# Smart_Lora_Node.net
KiCad netlist of a schematic drawn in Altium Designer
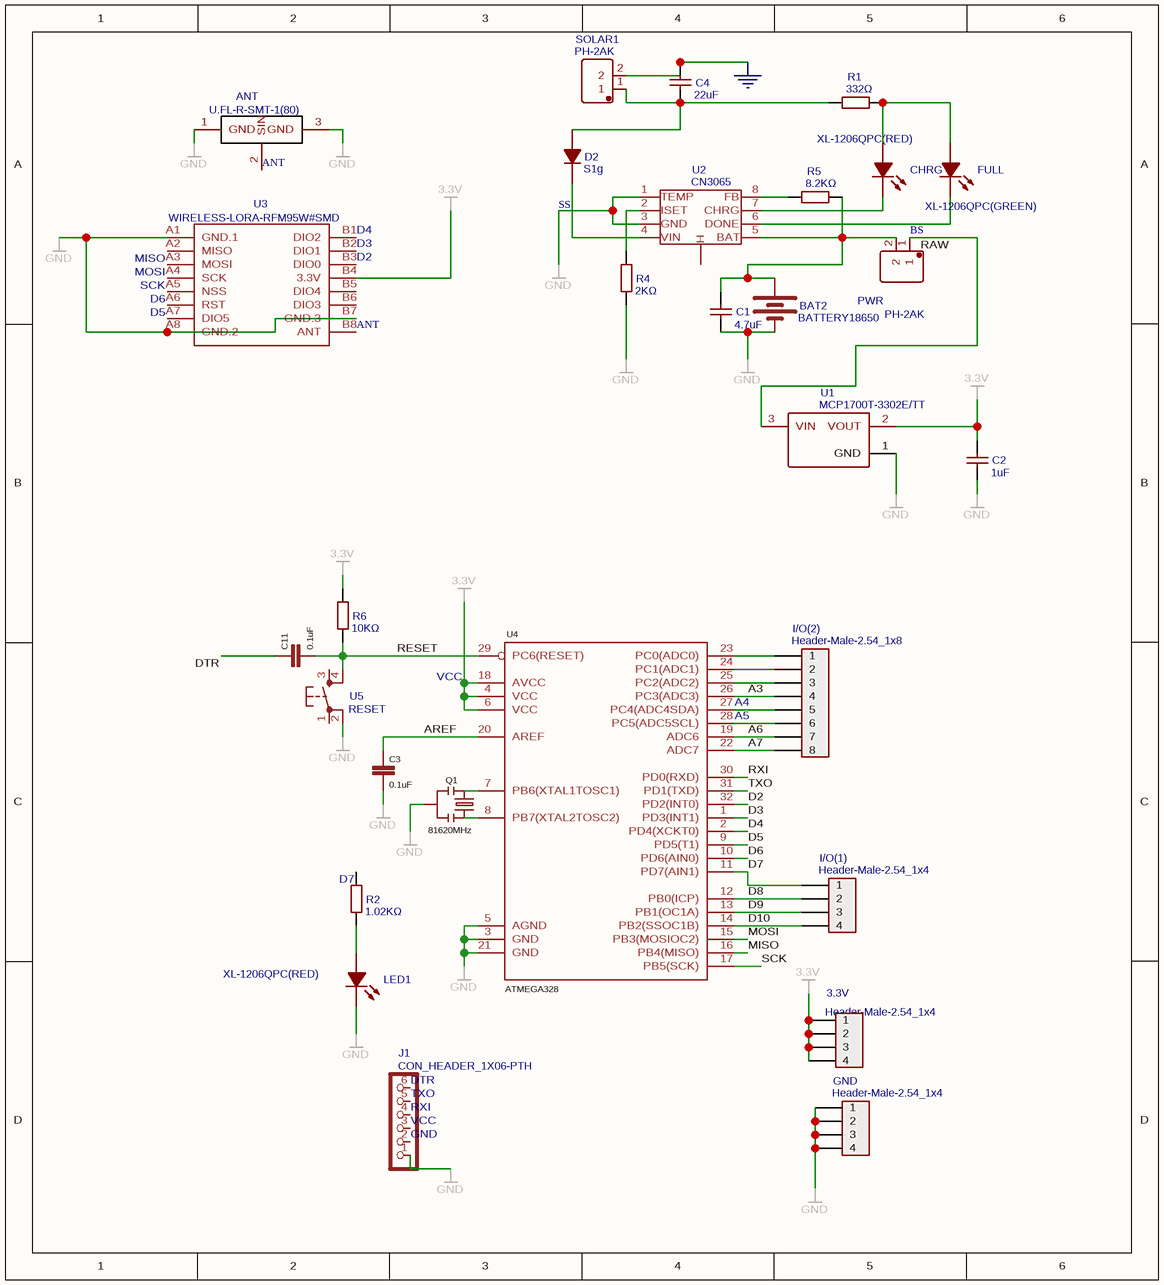
[diagram p0: Smart+Lora+Node.schdoc]

(export (version "E")
  (design (tool "Eeschema 10.0.6"))
  (components
    (comp (ref "3.3V")
      (value "Header-Male-2.54_1x4")
      (fields
        (field (name "BOM_MANUFACTURER PART") "Headers??Pins 1*4P")
        (field (name "BOM_SUPPLIER PART") "C59481")
      )
      (libsource (lib "altium-import") (part "root_0_Header-Male-2.54_1x4_"))
    )
    (comp (ref "ANT")
      (value "U.FL-R-SMT-1(80)")
      (fields (field (name "BOM_SUPPLIER PART") "C88374"))
      (libsource (lib "altium-import") (part "root_0_U.FL-R-SMT-1(80)_"))
    )
    (comp (ref "BAT2")
      (value "BATTERY18650")
      (description "Battery Holders")
      (fields (field (name "BOM_MANUFACTURER PART") "?") (field (name "CONTRIBUTOR") "SparkFun"))
      (libsource (lib "altium-import") (part "root_3_BATTERY18650_"))
    )
    (comp (ref "C1")
      (value "4.7uF")
      (fields
        (field (name "VOLTAGE") "50V")
        (field (name "TOLERANCE") "±10%")
        (field (name "BOM_MANUFACTURER PART") "1206B475K500NT")
      )
      (libsource (lib "altium-import") (part "root_1_4.7uF_"))
    )
    (comp (ref "C2")
      (value "1uF")
      (fields
        (field (name "VOLTAGE") "50V")
        (field (name "TOLERANCE") "±10%")
        (field (name "BOM_MANUFACTURER PART") "0805B105K500NT")
      )
      (libsource (lib "altium-import") (part "root_1_1uF_"))
    )
    (comp (ref "C3") (value "0.1uF") (libsource (lib "altium-import") (part "root_2_0.1uF_")))
    (comp (ref "C4")
      (value "22uF")
      (fields
        (field (name "VOLTAGE") "10V")
        (field (name "TOLERANCE") "±10%")
        (field (name "BOM_MANUFACTURER PART") "1206X226K100NT")
      )
      (libsource (lib "altium-import") (part "root_1_22uF_"))
    )
    (comp (ref "C11") (value "0.1uF") (libsource (lib "altium-import") (part "root_3_0.1uF_")))
    (comp (ref "CHRG")
      (value "XL-1206QPC(RED)")
      (fields (field (name "BOM_MANUFACTURER PART") "XL-1206QPC") (field (name "BOM_SUPPLIER PART") "C10781"))
      (libsource (lib "altium-import") (part "root_3_XL-1206QPC(RED)_"))
    )
    (comp (ref "D2")
      (value "S1g")
      (fields (field (name "BOM_SUPPLIER PART") "C19153"))
      (libsource (lib "altium-import") (part "root_3_S1g_"))
    )
    (comp (ref "FULL")
      (value "XL-1206QPC(GREEN)")
      (fields (field (name "BOM_MANUFACTURER PART") "XL-1206QPC") (field (name "BOM_SUPPLIER PART") "C10781"))
      (libsource (lib "altium-import") (part "root_3_XL-1206QPC(GREEN)_"))
    )
    (comp (ref "GND")
      (value "Header-Male-2.54_1x4")
      (fields
        (field (name "BOM_MANUFACTURER PART") "Headers??Pins 1*4P")
        (field (name "BOM_SUPPLIER PART") "C59481")
      )
      (libsource (lib "altium-import") (part "root_0_Header-Male-2.54_1x4_"))
    )
    (comp (ref "I/O(1)")
      (value "Header-Male-2.54_1x4")
      (fields
        (field (name "BOM_MANUFACTURER PART") "Headers??Pins 1*4P")
        (field (name "BOM_SUPPLIER PART") "C59481")
      )
      (libsource (lib "altium-import") (part "root_0_Header-Male-2.54_1x4_"))
    )
    (comp (ref "I/O(2)")
      (value "Header-Male-2.54_1x8")
      (fields
        (field (name "BOM_MANUFACTURER PART") "Header2.54mm 1*8P")
        (field (name "BOM_SUPPLIER PART") "C49256")
      )
      (libsource (lib "altium-import") (part "root_0_Header-Male-2.54_1x8_"))
    )
    (comp (ref "J1")
      (value "CON_HEADER_1X06-PTH")
      (fields (field (name "BOM_MANUFACTURER PART") "?") (field (name "CONTRIBUTOR") "DangerousPrototype"))
      (libsource (lib "altium-import") (part "root_2_CON_HEADER_1X06-PTH_"))
    )
    (comp (ref "LED1")
      (value "XL-1206QPC(RED)")
      (fields (field (name "BOM_MANUFACTURER PART") "XL-1206QPC") (field (name "BOM_SUPPLIER PART") "C10781"))
      (libsource (lib "altium-import") (part "root_3_XL-1206QPC(RED)_"))
    )
    (comp (ref "PWR")
      (value "PH-2AK")
      (fields (field (name "BOM_MANUFACTURER PART") "?") (field (name "BOM_SUPPLIER PART") "C8886"))
      (libsource (lib "altium-import") (part "root_3_PH-2AK_"))
    )
    (comp (ref "Q1") (value "81620MHz") (libsource (lib "altium-import") (part "root_3_81620MHz_")))
    (comp (ref "R1")
      (value "332Ω")
      (fields
        (field (name "POWER") "1/8W")
        (field (name "TOLERANCE") "±1%")
        (field (name "BOM_MANUFACTURER PART") "0805W8F3320T5E")
      )
      (libsource (lib "altium-import") (part "root_0_332Ω_"))
    )
    (comp (ref "R2")
      (value "1.02KΩ")
      (fields
        (field (name "POWER") "1/8W")
        (field (name "TOLERANCE") "±1%")
        (field (name "BOM_MANUFACTURER PART") "0805W8F1021T5E")
      )
      (libsource (lib "altium-import") (part "root_1_1.02KΩ_"))
    )
    (comp (ref "R4")
      (value "2KΩ")
      (fields
        (field (name "POWER") "1/8W")
        (field (name "TOLERANCE") "±5%")
        (field (name "BOM_MANUFACTURER PART") "0805W8J0202T5E")
      )
      (libsource (lib "altium-import") (part "root_1_2KΩ_"))
    )
    (comp (ref "R5")
      (value "8.2KΩ")
      (fields
        (field (name "POWER") "1/4W")
        (field (name "TOLERANCE") "±5%")
        (field (name "BOM_MANUFACTURER PART") "1206W4J0822T5E")
      )
      (libsource (lib "altium-import") (part "root_0_8.2KΩ_"))
    )
    (comp (ref "R6")
      (value "10KΩ")
      (fields
        (field (name "POWER") "1/8W")
        (field (name "TOLERANCE") "±5%")
        (field (name "BOM_MANUFACTURER PART") "0805W8J0103T5E")
      )
      (libsource (lib "altium-import") (part "root_1_10KΩ_"))
    )
    (comp (ref "SOLAR1")
      (value "PH-2AK")
      (fields (field (name "BOM_MANUFACTURER PART") "?") (field (name "BOM_SUPPLIER PART") "C8886"))
      (libsource (lib "altium-import") (part "root_2_PH-2AK_"))
    )
    (comp (ref "U1")
      (value "MCP1700T-3302E/TT")
      (fields (field (name "BOM_SUPPLIER PART") "C39051"))
      (libsource (lib "altium-import") (part "root_0_MCP1700T-3302E/TT_"))
    )
    (comp (ref "U2")
      (value "CN3065")
      (description "SMD PMIC;Liner;Li-Ion/Pol;Charge;4.2V;1-cell")
      (libsource (lib "altium-import") (part "root_0_CN3065_"))
    )
    (comp (ref "U3")
      (value "WIRELESS-LORA-RFM95W#SMD")
      (description "868915 MHz LoRa Radio Transceiver Module based on SX1276 chip")
      (fields
        (field (name "BOM_MANUFACTURER PART") "RFM95W-868S2")
        (field (name "BOM_SUPPLIER PART") "125-1259")
      )
      (libsource (lib "altium-import") (part "root_0_WIRELESS-LORA-RFM95W#SMD_"))
    )
    (comp (ref "U4") (value "ATMEGA328") (libsource (lib "altium-import") (part "root_0_ATMEGA328_")))
    (comp (ref "U5")
      (value "RESET")
      (description "Tactile Switch 4 Pins, SPST NO PTS645SM43SMTR92")
      (fields (field (name "BOM_MANUFACTURER PART") "?"))
      (libsource (lib "altium-import") (part "root_1_RESET_"))
    )
  )
  (nets
    (net (code "1") (name "/A3") (class "Default")
      (node (ref "I/O(2)") (pin "4") (pinfunction "4_4") (pintype "passive"))
      (node (ref "U4") (pin "26") (pinfunction "PC3(ADC3)_26") (pintype "passive"))
    )
    (net (code "2") (name "/A4") (class "Default")
      (node (ref "I/O(2)") (pin "5") (pinfunction "5_5") (pintype "passive"))
      (node (ref "U4") (pin "27") (pinfunction "PC4(ADC4SDA)_27") (pintype "passive"))
    )
    (net (code "3") (name "/A5") (class "Default")
      (node (ref "I/O(2)") (pin "6") (pinfunction "6_6") (pintype "passive"))
      (node (ref "U4") (pin "28") (pinfunction "PC5(ADC5SCL)_28") (pintype "passive"))
    )
    (net (code "4") (name "/A6") (class "Default")
      (node (ref "I/O(2)") (pin "7") (pinfunction "7_7") (pintype "passive"))
      (node (ref "U4") (pin "19") (pinfunction "ADC6_19") (pintype "passive"))
    )
    (net (code "5") (name "/A7") (class "Default")
      (node (ref "I/O(2)") (pin "8") (pinfunction "8_8") (pintype "passive"))
      (node (ref "U4") (pin "22") (pinfunction "ADC7_22") (pintype "passive"))
    )
    (net (code "6") (name "/ANT") (class "Default")
      (node (ref "ANT") (pin "2") (pinfunction "SIN_2") (pintype "passive"))
      (node (ref "U3") (pin "B8") (pinfunction "ANT_B8") (pintype "passive"))
    )
    (net (code "7") (name "/AREF") (class "Default")
      (node (ref "C3") (pin "2") (pinfunction "2_2") (pintype "passive"))
      (node (ref "U4") (pin "20") (pinfunction "AREF_20") (pintype "passive"))
    )
    (net (code "8") (name "/BS") (class "Default")
      (node (ref "PWR") (pin "1") (pinfunction "1_1") (pintype "passive"))
      (node (ref "U1") (pin "3") (pinfunction "VIN_3") (pintype "passive"))
    )
    (net (code "9") (name "/D2") (class "Default")
      (node (ref "U3") (pin "B3") (pinfunction "DIO0_B3") (pintype "passive"))
      (node (ref "U4") (pin "32") (pinfunction "PD2(INT0)_32") (pintype "passive"))
    )
    (net (code "10") (name "/D3") (class "Default")
      (node (ref "U3") (pin "B2") (pinfunction "DIO1_B2") (pintype "passive"))
      (node (ref "U4") (pin "1") (pinfunction "PD3(INT1)_1") (pintype "passive"))
    )
    (net (code "11") (name "/D4") (class "Default")
      (node (ref "U3") (pin "B1") (pinfunction "DIO2_B1") (pintype "passive"))
      (node (ref "U4") (pin "2") (pinfunction "PD4(XCKT0)_2") (pintype "passive"))
    )
    (net (code "12") (name "/D5") (class "Default")
      (node (ref "U3") (pin "A6") (pinfunction "RST_A6") (pintype "passive"))
      (node (ref "U4") (pin "9") (pinfunction "PD5(T1)_9") (pintype "passive"))
    )
    (net (code "13") (name "/D6") (class "Default")
      (node (ref "U3") (pin "A5") (pinfunction "NSS_A5") (pintype "passive"))
      (node (ref "U4") (pin "10") (pinfunction "PD6(AIN0)_10") (pintype "passive"))
    )
    (net (code "14") (name "/D7") (class "Default")
      (node (ref "I/O(1)") (pin "1") (pinfunction "1_1") (pintype "passive"))
      (node (ref "R2") (pin "2") (pinfunction "2_2") (pintype "passive"))
      (node (ref "U4") (pin "11") (pinfunction "PD7(AIN1)_11") (pintype "passive"))
    )
    (net (code "15") (name "/D8") (class "Default")
      (node (ref "I/O(1)") (pin "2") (pinfunction "2_2") (pintype "passive"))
      (node (ref "U4") (pin "12") (pinfunction "PB0(ICP)_12") (pintype "passive"))
    )
    (net (code "16") (name "/D9") (class "Default")
      (node (ref "I/O(1)") (pin "3") (pinfunction "3_3") (pintype "passive"))
      (node (ref "U4") (pin "13") (pinfunction "PB1(OC1A)_13") (pintype "passive"))
    )
    (net (code "17") (name "/D10") (class "Default")
      (node (ref "I/O(1)") (pin "4") (pinfunction "4_4") (pintype "passive"))
      (node (ref "U4") (pin "14") (pinfunction "PB2(SSOC1B)_14") (pintype "passive"))
    )
    (net (code "18") (name "/DTR") (class "Default")
      (node (ref "C11") (pin "2") (pinfunction "2_2") (pintype "passive"))
      (node (ref "J1") (pin "6") (pinfunction "6_6") (pintype "passive"))
    )
    (net (code "19") (name "/MISO") (class "Default")
      (node (ref "U3") (pin "A2") (pinfunction "MISO_A2") (pintype "passive"))
      (node (ref "U4") (pin "16") (pinfunction "PB4(MISO)_16") (pintype "passive"))
    )
    (net (code "20") (name "/MOSI") (class "Default")
      (node (ref "U3") (pin "A3") (pinfunction "MOSI_A3") (pintype "passive"))
      (node (ref "U4") (pin "15") (pinfunction "PB3(MOSIOC2)_15") (pintype "passive"))
    )
    (net (code "21") (name "/RESET") (class "Default")
      (node (ref "C11") (pin "1") (pinfunction "1_1") (pintype "passive"))
      (node (ref "R6") (pin "1") (pinfunction "1_1") (pintype "passive"))
      (node (ref "U4") (pin "29") (pinfunction "PC6(RESET)_29") (pintype "passive"))
      (node (ref "U5") (pin "4") (pinfunction "4_4") (pintype "passive"))
    )
    (net (code "22") (name "/RXI") (class "Default")
      (node (ref "J1") (pin "4") (pinfunction "4_4") (pintype "passive"))
      (node (ref "U4") (pin "30") (pinfunction "PD0(RXD)_30") (pintype "passive"))
    )
    (net (code "23") (name "/SCK") (class "Default")
      (node (ref "U3") (pin "A4") (pinfunction "SCK_A4") (pintype "passive"))
      (node (ref "U4") (pin "17") (pinfunction "PB5(SCK)_17") (pintype "passive"))
    )
    (net (code "24") (name "/SS") (class "Default")
      (node (ref "D2") (pin "2") (pinfunction "K_2") (pintype "passive"))
      (node (ref "U2") (pin "4") (pinfunction "VIN_4") (pintype "passive"))
    )
    (net (code "25") (name "/TXO") (class "Default")
      (node (ref "J1") (pin "5") (pinfunction "5_5") (pintype "passive"))
      (node (ref "U4") (pin "31") (pinfunction "PD1(TXD)_31") (pintype "passive"))
    )
    (net (code "26") (name "3.3V") (class "Default")
      (node (ref "3.3V") (pin "1") (pinfunction "1_1") (pintype "passive"))
      (node (ref "3.3V") (pin "2") (pinfunction "2_2") (pintype "passive"))
      (node (ref "3.3V") (pin "3") (pinfunction "3_3") (pintype "passive"))
      (node (ref "3.3V") (pin "4") (pinfunction "4_4") (pintype "passive"))
      (node (ref "C2") (pin "2") (pinfunction "2_2") (pintype "passive"))
      (node (ref "J1") (pin "3") (pinfunction "3_3") (pintype "passive"))
      (node (ref "R6") (pin "2") (pinfunction "2_2") (pintype "passive"))
      (node (ref "U1") (pin "2") (pinfunction "VOUT_2") (pintype "passive"))
      (node (ref "U3") (pin "B4") (pinfunction "3.3V_B4") (pintype "passive"))
      (node (ref "U4") (pin "18") (pinfunction "AVCC_18") (pintype "passive"))
      (node (ref "U4") (pin "4") (pinfunction "VCC_4") (pintype "passive"))
      (node (ref "U4") (pin "6") (pinfunction "VCC_6") (pintype "passive"))
    )
    (net (code "27") (name "GND") (class "Default")
      (node (ref "ANT") (pin "1") (pinfunction "GND_1") (pintype "passive"))
      (node (ref "ANT") (pin "3") (pinfunction "GND_3") (pintype "passive"))
      (node (ref "BAT2") (pin "-GND") (pinfunction "-_-GND") (pintype "passive"))
      (node (ref "C1") (pin "1") (pinfunction "1_1") (pintype "passive"))
      (node (ref "C2") (pin "1") (pinfunction "1_1") (pintype "passive"))
      (node (ref "C3") (pin "1") (pinfunction "1_1") (pintype "passive"))
      (node (ref "C4") (pin "2") (pinfunction "2_2") (pintype "passive"))
      (node (ref "GND") (pin "1") (pinfunction "1_1") (pintype "passive"))
      (node (ref "GND") (pin "2") (pinfunction "2_2") (pintype "passive"))
      (node (ref "GND") (pin "3") (pinfunction "3_3") (pintype "passive"))
      (node (ref "GND") (pin "4") (pinfunction "4_4") (pintype "passive"))
      (node (ref "J1") (pin "1") (pinfunction "1_1") (pintype "passive"))
      (node (ref "J1") (pin "2") (pinfunction "2_2") (pintype "passive"))
      (node (ref "LED1") (pin "1") (pinfunction "K_1") (pintype "passive"))
      (node (ref "Q1") (pin "2") (pinfunction "2_2") (pintype "passive"))
      (node (ref "R4") (pin "1") (pinfunction "1_1") (pintype "passive"))
      (node (ref "SOLAR1") (pin "2") (pinfunction "2_2") (pintype "passive"))
      (node (ref "U1") (pin "1") (pinfunction "GND_1") (pintype "passive"))
      (node (ref "U2") (pin "1") (pinfunction "TEMP_1") (pintype "passive"))
      (node (ref "U2") (pin "3") (pinfunction "GND_3") (pintype "passive"))
      (node (ref "U3") (pin "A1") (pinfunction "GND.1_A1") (pintype "passive"))
      (node (ref "U3") (pin "A8") (pinfunction "GND.2_A8") (pintype "passive"))
      (node (ref "U3") (pin "B7") (pinfunction "GND.3_B7") (pintype "passive"))
      (node (ref "U4") (pin "21") (pinfunction "GND_21") (pintype "passive"))
      (node (ref "U4") (pin "3") (pinfunction "GND_3") (pintype "passive"))
      (node (ref "U4") (pin "5") (pinfunction "AGND_5") (pintype "passive"))
      (node (ref "U5") (pin "2") (pinfunction "2_2") (pintype "passive"))
    )
    (net (code "28") (name "Net-(BAT2-+)") (class "Default")
      (node (ref "BAT2") (pin "+BAT") (pinfunction "+_+BAT") (pintype "passive"))
      (node (ref "C1") (pin "2") (pinfunction "2_2") (pintype "passive"))
      (node (ref "PWR") (pin "2") (pinfunction "2_2") (pintype "passive"))
      (node (ref "R5") (pin "2") (pinfunction "2_2") (pintype "passive"))
      (node (ref "U2") (pin "5") (pinfunction "BAT_5") (pintype "passive"))
    )
    (net (code "29") (name "Net-(CHRG-A)") (class "Default")
      (node (ref "CHRG") (pin "2") (pinfunction "A_2") (pintype "passive"))
      (node (ref "FULL") (pin "2") (pinfunction "A_2") (pintype "passive"))
      (node (ref "R1") (pin "2") (pinfunction "2_2") (pintype "passive"))
    )
    (net (code "30") (name "Net-(CHRG-K)") (class "Default")
      (node (ref "CHRG") (pin "1") (pinfunction "K_1") (pintype "passive"))
      (node (ref "U2") (pin "7") (pinfunction "CHRG_7") (pintype "passive"))
    )
    (net (code "31") (name "Net-(D2-A)") (class "Default")
      (node (ref "C4") (pin "1") (pinfunction "1_1") (pintype "passive"))
      (node (ref "D2") (pin "1") (pinfunction "A_1") (pintype "passive"))
      (node (ref "R1") (pin "1") (pinfunction "1_1") (pintype "passive"))
      (node (ref "SOLAR1") (pin "1") (pinfunction "1_1") (pintype "passive"))
    )
    (net (code "32") (name "Net-(FULL-K)") (class "Default")
      (node (ref "FULL") (pin "1") (pinfunction "K_1") (pintype "passive"))
      (node (ref "U2") (pin "6") (pinfunction "DONE_6") (pintype "passive"))
    )
    (net (code "33") (name "Net-(LED1-A)") (class "Default")
      (node (ref "LED1") (pin "2") (pinfunction "A_2") (pintype "passive"))
      (node (ref "R2") (pin "1") (pinfunction "1_1") (pintype "passive"))
    )
    (net (code "34") (name "Net-(U2-FB)") (class "Default")
      (node (ref "R5") (pin "1") (pinfunction "1_1") (pintype "passive"))
      (node (ref "U2") (pin "8") (pinfunction "FB_8") (pintype "passive"))
    )
    (net (code "35") (name "Net-(U2-ISET)") (class "Default")
      (node (ref "R4") (pin "2") (pinfunction "2_2") (pintype "passive"))
      (node (ref "U2") (pin "2") (pinfunction "ISET_2") (pintype "passive"))
    )
    (net (code "36") (name "Net-(U4-PB6(XTAL1TOSC1))") (class "Default")
      (node (ref "Q1") (pin "1") (pinfunction "1_1") (pintype "passive"))
      (node (ref "U4") (pin "7") (pinfunction "PB6(XTAL1TOSC1)_7") (pintype "passive"))
    )
    (net (code "37") (name "Net-(U4-PB7(XTAL2TOSC2))") (class "Default")
      (node (ref "Q1") (pin "3") (pinfunction "3_3") (pintype "passive"))
      (node (ref "U4") (pin "8") (pinfunction "PB7(XTAL2TOSC2)_8") (pintype "passive"))
    )
    (net (code "38") (name "Net-(U4-PC0(ADC0))") (class "Default")
      (node (ref "I/O(2)") (pin "1") (pinfunction "1_1") (pintype "passive"))
      (node (ref "U4") (pin "23") (pinfunction "PC0(ADC0)_23") (pintype "passive"))
    )
    (net (code "39") (name "Net-(U4-PC1(ADC1))") (class "Default")
      (node (ref "I/O(2)") (pin "2") (pinfunction "2_2") (pintype "passive"))
      (node (ref "U4") (pin "24") (pinfunction "PC1(ADC1)_24") (pintype "passive"))
    )
    (net (code "40") (name "Net-(U4-PC2(ADC2))") (class "Default")
      (node (ref "I/O(2)") (pin "3") (pinfunction "3_3") (pintype "passive"))
      (node (ref "U4") (pin "25") (pinfunction "PC2(ADC2)_25") (pintype "passive"))
    )
    (net (code "41") (name "unconnected-(U2-H-PadHEAT)") (class "Default")
      (node (ref "U2") (pin "HEAT") (pinfunction "H_HEAT") (pintype "passive"))
    )
    (net (code "42") (name "unconnected-(U3-DIO3-PadB6)") (class "Default")
      (node (ref "U3") (pin "B6") (pinfunction "DIO3_B6") (pintype "passive"))
    )
    (net (code "43") (name "unconnected-(U3-DIO4-PadB5)") (class "Default")
      (node (ref "U3") (pin "B5") (pinfunction "DIO4_B5") (pintype "passive"))
    )
    (net (code "44") (name "unconnected-(U3-DIO5-PadA7)") (class "Default")
      (node (ref "U3") (pin "A7") (pinfunction "DIO5_A7") (pintype "passive"))
    )
    (net (code "45") (name "unconnected-(U5-Pad1)") (class "Default")
      (node (ref "U5") (pin "1") (pinfunction "1_1") (pintype "passive"))
    )
    (net (code "46") (name "unconnected-(U5-Pad3)") (class "Default")
      (node (ref "U5") (pin "3") (pinfunction "3_3") (pintype "passive"))
    )
  )
)
